# EVB-ANNA-B5_SCHEM_0004_Connectors_Memory.net
KiCad netlist of a schematic drawn in Altium Designer
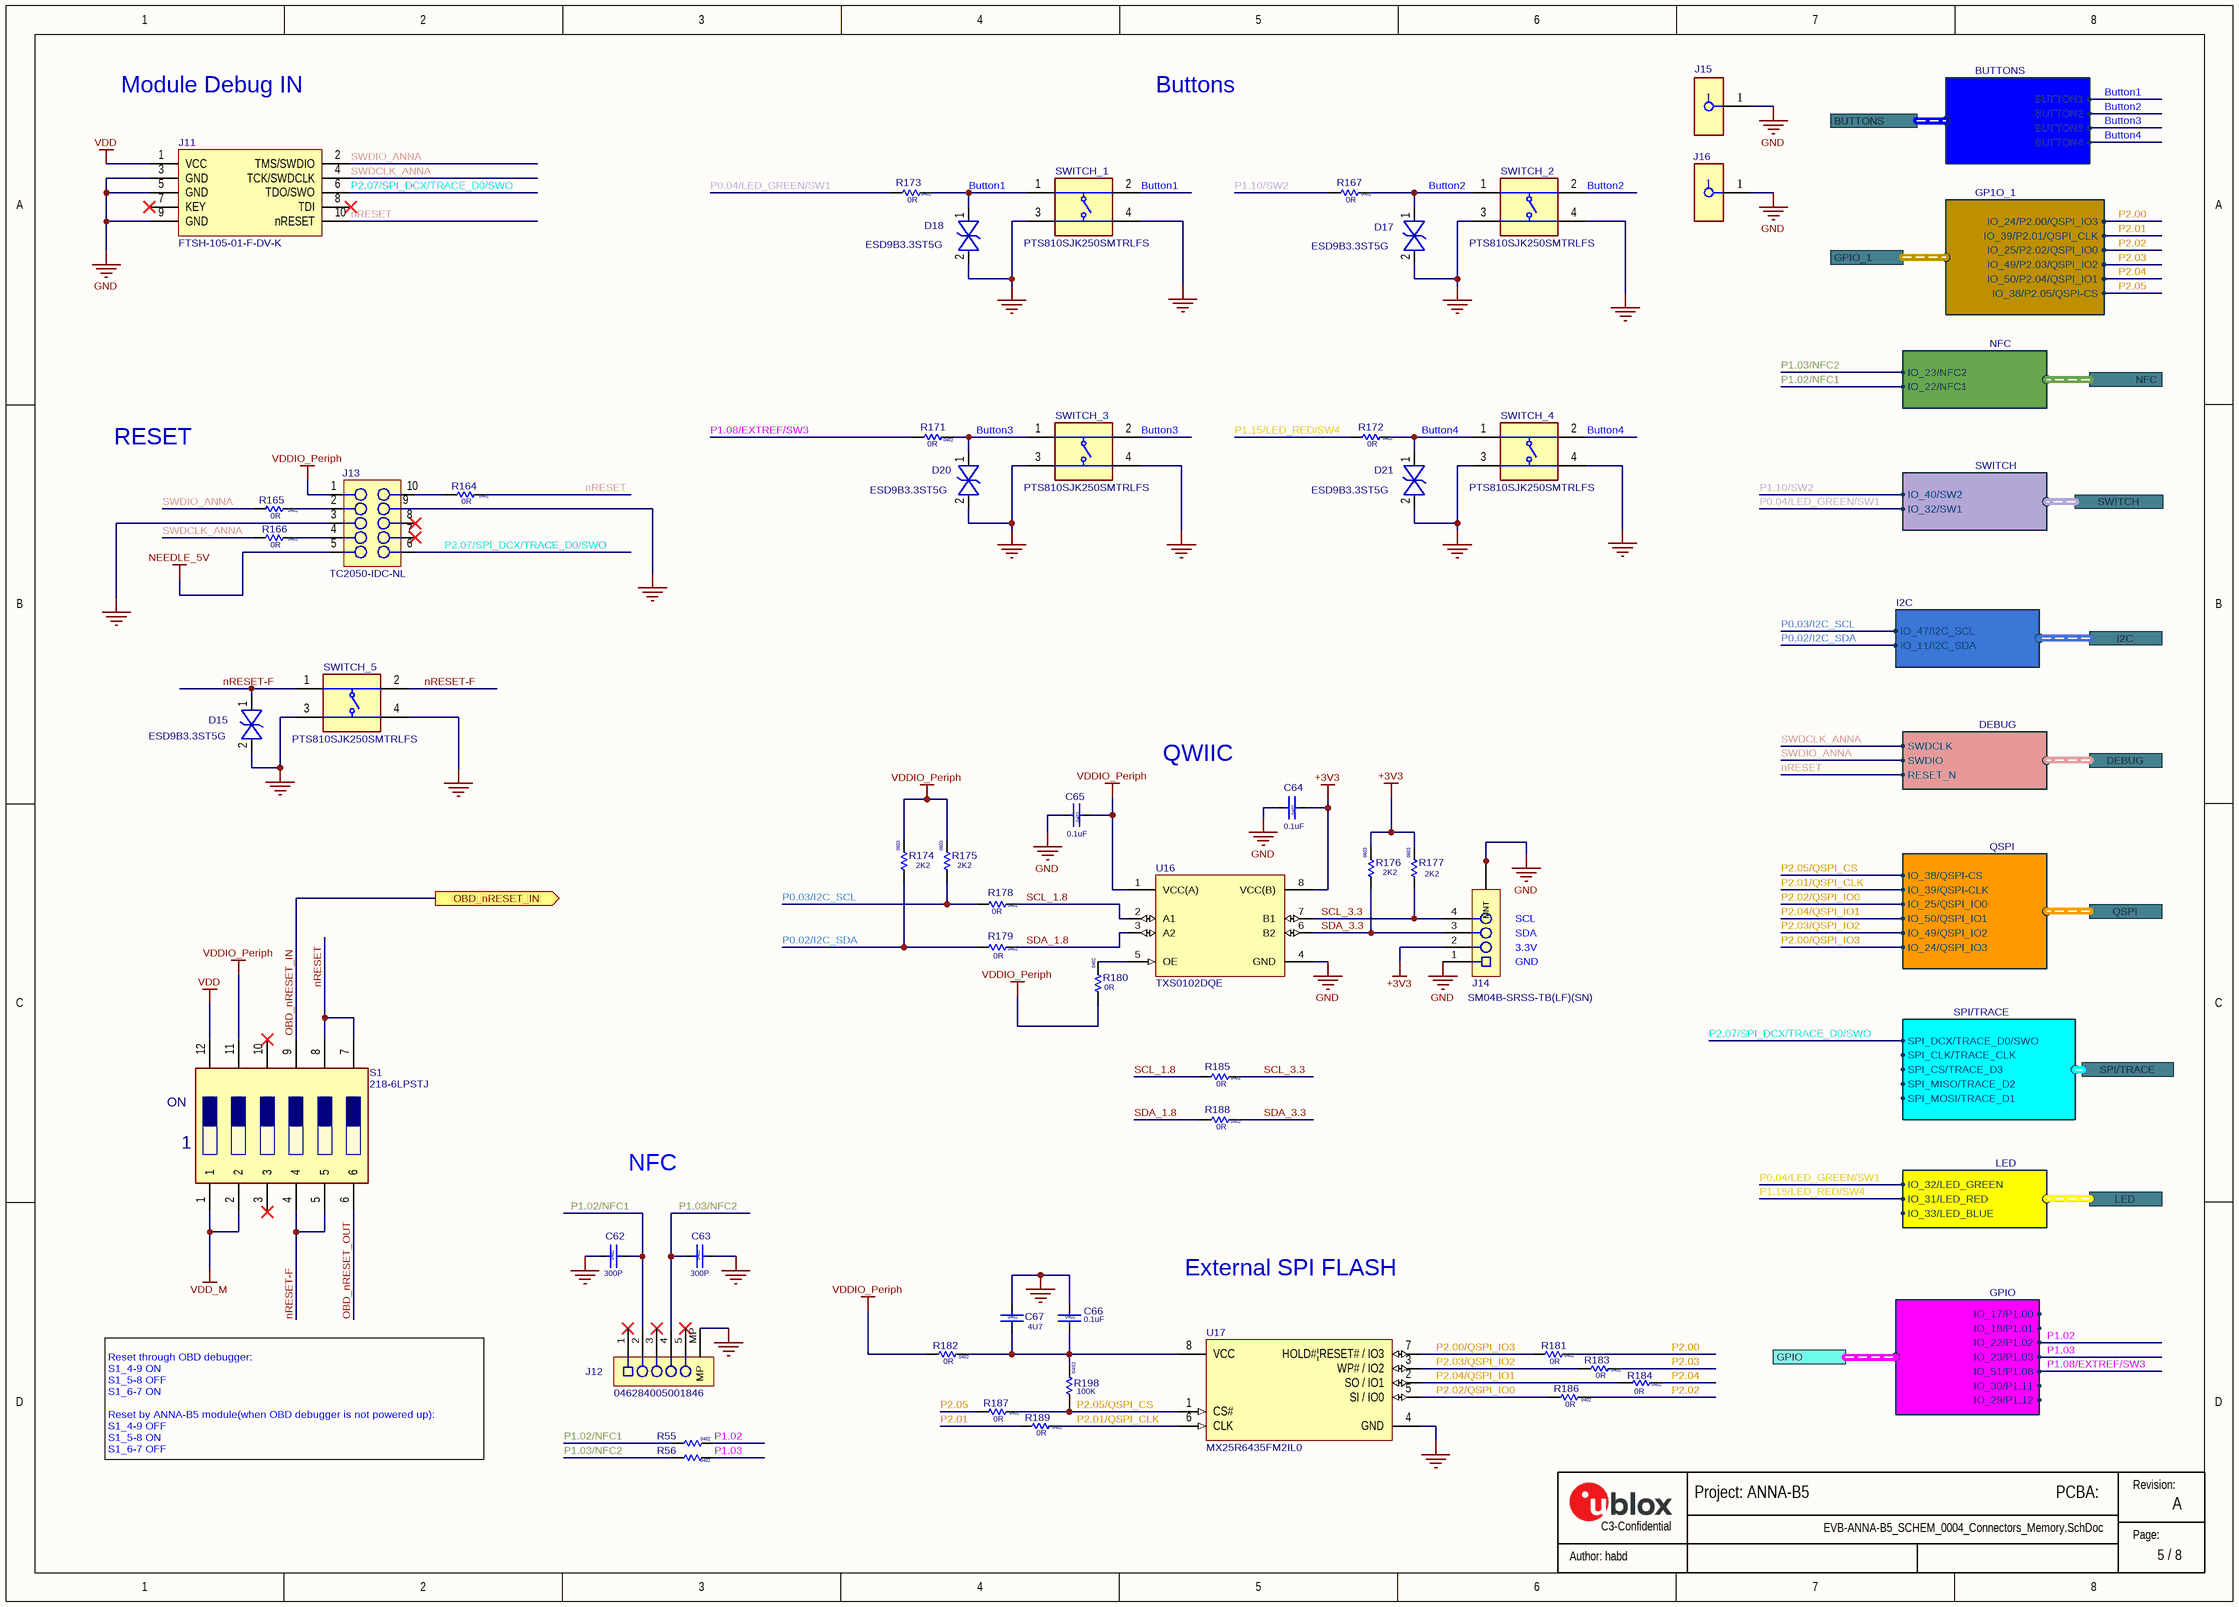
[diagram p0: EVB-ANNA-B5_SCHEM_0004_Connectors_Memory.SchDoc]

(export (version "E")
  (design (tool "Eeschema 10.0.6"))
  (components
    (comp (ref "C62")
      (value "300P")
      (footprint "Cap 0402 HD")
      (description "CAP CER C0G 0402 300P 50V")
      (fields
        (field (name "SIZE") "0402")
        (field (name "PART NUMBER") "UBXH01-0000594")
        (field (name "MANUFACTURER") "Murata Manufacturing Company, Ltd.")
        (field (name "EDITOR") "eric.moog")
      )
      (libsource (lib "UBX_Parts_DB_Lib") (part "Cap Chip"))
    )
    (comp (ref "C63")
      (value "300P")
      (footprint "Cap 0402 HD")
      (description "CAP CER C0G 0402 300P 50V")
      (fields
        (field (name "SIZE") "0402")
        (field (name "PART NUMBER") "UBXH01-0000594")
        (field (name "MANUFACTURER") "Murata Manufacturing Company, Ltd.")
        (field (name "EDITOR") "eric.moog")
      )
      (libsource (lib "UBX_Parts_DB_Lib") (part "Cap Chip"))
    )
    (comp (ref "C64")
      (value "0.1uF")
      (footprint "Cap 0402 HD")
      (description "Cap, Ceramic 0.1uF 10V 10% X5R 0402")
      (fields
        (field (name "SIZE") "0402")
        (field (name "PART NUMBER") "120-00016")
        (field (name "MANUFACTURER") "Murata Electronics North America")
      )
      (libsource (lib "Arena_Parts_DB_Lib") (part "Cap Chip"))
    )
    (comp (ref "C65")
      (value "0.1uF")
      (footprint "Cap 0402 HD")
      (description "Cap, Ceramic 0.1uF 10V 10% X5R 0402")
      (fields
        (field (name "SIZE") "0402")
        (field (name "PART NUMBER") "120-00016")
        (field (name "MANUFACTURER") "Murata Electronics North America")
      )
      (libsource (lib "Arena_Parts_DB_Lib") (part "Cap Chip"))
    )
    (comp (ref "C66")
      (value "0.1uF")
      (footprint "Cap 0402 HD")
      (description "Cap, Ceramic 0.1uF 10V 10% X5R 0402")
      (fields
        (field (name "SIZE") "0402")
        (field (name "PART NUMBER") "120-00016")
        (field (name "MANUFACTURER") "Murata Electronics North America")
      )
      (libsource (lib "Arena_Parts_DB_Lib") (part "Cap Chip"))
    )
    (comp (ref "C67")
      (value "4U7")
      (footprint "Cap 0402 HD")
      (description "CAP CER X5R 0402 4U7 20% 10V")
      (fields
        (field (name "SIZE") "0402")
        (field (name "PART NUMBER") "UBXH01-0000243")
        (field (name "TOLERANCE") "20%")
        (field (name "EDITOR") "martin.pilik")
        (field (name "RELEASED BY") "fabrice.bret-dibat")
      )
      (libsource (lib "UBX_Parts_DB_Lib") (part "Cap Chip"))
    )
    (comp (ref "D15")
      (value "110-00019")
      (footprint "SOD-923")
      (description "ESD9B3.3ST5G")
      (fields
        (field (name "MANUFACTURER") "ON Semiconductor")
        (field (name "MANUFACTURER P/N") "ESD9B3.3ST5G")
        (field (name "VOLTAGE") "3.3V")
      )
      (libsource (lib "Arena_Parts_DB_Lib") (part "Diode_TVS"))
    )
    (comp (ref "D17")
      (value "110-00019")
      (footprint "SOD-923")
      (description "ESD9B3.3ST5G")
      (fields
        (field (name "MANUFACTURER") "ON Semiconductor")
        (field (name "MANUFACTURER P/N") "ESD9B3.3ST5G")
        (field (name "VOLTAGE") "3.3V")
      )
      (libsource (lib "Arena_Parts_DB_Lib") (part "Diode_TVS"))
    )
    (comp (ref "D18")
      (value "110-00019")
      (footprint "SOD-923")
      (description "ESD9B3.3ST5G")
      (fields
        (field (name "MANUFACTURER") "ON Semiconductor")
        (field (name "MANUFACTURER P/N") "ESD9B3.3ST5G")
        (field (name "VOLTAGE") "3.3V")
      )
      (libsource (lib "Arena_Parts_DB_Lib") (part "Diode_TVS"))
    )
    (comp (ref "D20")
      (value "110-00019")
      (footprint "SOD-923")
      (description "ESD9B3.3ST5G")
      (fields
        (field (name "MANUFACTURER") "ON Semiconductor")
        (field (name "MANUFACTURER P/N") "ESD9B3.3ST5G")
        (field (name "VOLTAGE") "3.3V")
      )
      (libsource (lib "Arena_Parts_DB_Lib") (part "Diode_TVS"))
    )
    (comp (ref "D21")
      (value "110-00019")
      (footprint "SOD-923")
      (description "ESD9B3.3ST5G")
      (fields
        (field (name "MANUFACTURER") "ON Semiconductor")
        (field (name "MANUFACTURER P/N") "ESD9B3.3ST5G")
        (field (name "VOLTAGE") "3.3V")
      )
      (libsource (lib "Arena_Parts_DB_Lib") (part "Diode_TVS"))
    )
    (comp (ref "J11")
      (value "130-00099")
      (footprint "HDR.050P-10Pin-2x5-SMT_Key")
      (description "Header 0.05\" 10Pin 2Row SMD Black")
      (fields (field (name "MANUFACTURER") "Samtec") (field (name "MANUFACTURER P/N") "FTSH-105-01-F-DV-K"))
      (libsource (lib "Arena_Parts_DB_Lib") (part "JTAG-10Pin"))
    )
    (comp (ref "J12")
      (value "UBXH04-0000798")
      (footprint "AVX/Kyocera - 046284005001846")
      (description "0.50MM PITCH SMD RA FFC FPC CONN 5 -PIN 50V 400mA")
      (fields
        (field (name "MANUFACTURER P/N") "046284005001846")
        (field (name "VOLTAGE") "50V")
        (field (name "MANUFACTURER") "AVX")
        (field (name "EDITOR") "eric.moog")
      )
      (libsource (lib "UBX_Parts_DB_Lib") (part "CON-5Pin_1Row-046284005001846"))
    )
    (comp (ref "J13")
      (value "TC2050-IDC-NL")
      (footprint "TC2050-IDC-NL")
      (description "CON PADS FOR CBL PLUG-OF-NAILS 10-PIN NO LEGS")
      (fields
        (field (name "MANUFACTURER P/N") "TC2050-IDC-NL")
        (field (name "MANUFACTURER") "TAG Connect")
        (field (name "ADDED BY") "Paul B")
      )
      (libsource (lib "LEGACY_Rigado_AltiumLib") (part "CON-10Pin_2Row_ALT"))
    )
    (comp (ref "J14")
      (value "UBXH04-0000797")
      (footprint "SM04B-SRSS-TB")
      (description "CONN JST SH SERIES SMT 4 POS MALE 1MM RA 50V 1A")
      (fields
        (field (name "MANUFACTURER PART NUMBER 1") "SM04B-SRSS-TB(LF)(SN)")
        (field (name "VOLTAGE") "None")
        (field (name "MANUFACTURER") "JST")
        (field (name "EDITOR") "eric.moog")
      )
      (libsource (lib "UBX_Parts_DB_Lib") (part "SM04B-SRSS-TB"))
    )
    (comp (ref "J15")
      (value "~")
      (footprint "Harwin_0_MFG")
      (libsource (lib "Conn_Harwin_S1751-46R_eec") (part "S1751-46R"))
    )
    (comp (ref "J16")
      (value "~")
      (footprint "Harwin_0_MFG")
      (libsource (lib "Conn_Harwin_S1751-46R_eec") (part "S1751-46R"))
    )
    (comp (ref "R55")
      (value "UBXH18-0003002")
      (footprint "RES 0402 HD")
      (description "RES THICK FILM CHIP 0402 0R 0 100mW")
      (fields
        (field (name "SIZE") "0402")
        (field (name "TOLERANCE") "0")
        (field (name "MANUFACTURER") "KOA")
        (field (name "EDITOR") "charlotte.biber")
        (field (name "RELEASED BY") "peter.mueller")
      )
      (libsource (lib "UBX_Parts_DB_Lib") (part "Res sm"))
    )
    (comp (ref "R56")
      (value "UBXH18-0003002")
      (footprint "RES 0402 HD")
      (description "RES THICK FILM CHIP 0402 0R 0 100mW")
      (fields
        (field (name "SIZE") "0402")
        (field (name "TOLERANCE") "0")
        (field (name "MANUFACTURER") "KOA")
        (field (name "EDITOR") "charlotte.biber")
        (field (name "RELEASED BY") "peter.mueller")
      )
      (libsource (lib "UBX_Parts_DB_Lib") (part "Res sm"))
    )
    (comp (ref "R164")
      (value "0R")
      (footprint "RES 0402 HD")
      (description "RES THICK FILM CHIP 0402 0R 0 100mW")
      (fields
        (field (name "SIZE") "0402")
        (field (name "PART NUMBER") "UBXH18-0003002")
        (field (name "TOLERANCE") "0")
        (field (name "EDITOR") "charlotte.biber")
        (field (name "RELEASED BY") "peter.mueller")
      )
      (libsource (lib "UBX_Parts_DB_Lib") (part "Res sm"))
    )
    (comp (ref "R165")
      (value "0R")
      (footprint "RES 0402 HD")
      (description "RES THICK FILM CHIP 0402 0R 0 100mW")
      (fields
        (field (name "SIZE") "0402")
        (field (name "PART NUMBER") "UBXH18-0003002")
        (field (name "TOLERANCE") "0")
        (field (name "EDITOR") "charlotte.biber")
        (field (name "RELEASED BY") "peter.mueller")
      )
      (libsource (lib "UBX_Parts_DB_Lib") (part "Res sm"))
    )
    (comp (ref "R166")
      (value "0R")
      (footprint "RES 0402 HD")
      (description "RES THICK FILM CHIP 0402 0R 0 100mW")
      (fields
        (field (name "SIZE") "0402")
        (field (name "PART NUMBER") "UBXH18-0003002")
        (field (name "TOLERANCE") "0")
        (field (name "EDITOR") "charlotte.biber")
        (field (name "RELEASED BY") "peter.mueller")
      )
      (libsource (lib "UBX_Parts_DB_Lib") (part "Res sm"))
    )
    (comp (ref "R167")
      (value "0R")
      (footprint "RES 0402 HD")
      (description "RES THICK FILM CHIP 0402 0R 0 100mW")
      (fields
        (field (name "SIZE") "0402")
        (field (name "PART NUMBER") "UBXH18-0003002")
        (field (name "TOLERANCE") "0")
        (field (name "EDITOR") "charlotte.biber")
        (field (name "RELEASED BY") "peter.mueller")
      )
      (libsource (lib "UBX_Parts_DB_Lib") (part "Res sm"))
    )
    (comp (ref "R171")
      (value "0R")
      (footprint "RES 0402 HD")
      (description "RES THICK FILM CHIP 0402 0R 0 100mW")
      (fields
        (field (name "SIZE") "0402")
        (field (name "PART NUMBER") "UBXH18-0003002")
        (field (name "TOLERANCE") "0")
        (field (name "EDITOR") "charlotte.biber")
        (field (name "RELEASED BY") "peter.mueller")
      )
      (libsource (lib "UBX_Parts_DB_Lib") (part "Res sm"))
    )
    (comp (ref "R172")
      (value "0R")
      (footprint "RES 0402 HD")
      (description "RES THICK FILM CHIP 0402 0R 0 100mW")
      (fields
        (field (name "SIZE") "0402")
        (field (name "PART NUMBER") "UBXH18-0003002")
        (field (name "TOLERANCE") "0")
        (field (name "EDITOR") "charlotte.biber")
        (field (name "RELEASED BY") "peter.mueller")
      )
      (libsource (lib "UBX_Parts_DB_Lib") (part "Res sm"))
    )
    (comp (ref "R173")
      (value "0R")
      (footprint "RES 0402 HD")
      (description "RES THICK FILM CHIP 0402 0R 0 100mW")
      (fields
        (field (name "SIZE") "0402")
        (field (name "PART NUMBER") "UBXH18-0003002")
        (field (name "TOLERANCE") "0")
        (field (name "EDITOR") "charlotte.biber")
        (field (name "RELEASED BY") "peter.mueller")
      )
      (libsource (lib "UBX_Parts_DB_Lib") (part "Res sm"))
    )
    (comp (ref "R174")
      (value "2K2")
      (footprint "RES_0603_1700Lx950Wx600H_600x1000Pad_800G_FLX")
      (description "RES THICK FILM CHIP 0603 2K2 5% 100mW")
      (fields
        (field (name "SIZE") "0603")
        (field (name "PART NUMBER") "UBXH18-0007081")
        (field (name "TOLERANCE") "5%")
        (field (name "EDITOR") "roland.rust")
        (field (name "RELEASED BY") "roland.rust")
      )
      (libsource (lib "UBX_Parts_DB_Lib") (part "Res sm"))
    )
    (comp (ref "R175")
      (value "2K2")
      (footprint "RES_0603_1700Lx950Wx600H_600x1000Pad_800G_FLX")
      (description "RES THICK FILM CHIP 0603 2K2 5% 100mW")
      (fields
        (field (name "SIZE") "0603")
        (field (name "PART NUMBER") "UBXH18-0007081")
        (field (name "TOLERANCE") "5%")
        (field (name "EDITOR") "roland.rust")
        (field (name "RELEASED BY") "roland.rust")
      )
      (libsource (lib "UBX_Parts_DB_Lib") (part "Res sm"))
    )
    (comp (ref "R176")
      (value "2K2")
      (footprint "RES_0603_1700Lx950Wx600H_600x1000Pad_800G_FLX")
      (description "RES THICK FILM CHIP 0603 2K2 5% 100mW")
      (fields
        (field (name "SIZE") "0603")
        (field (name "PART NUMBER") "UBXH18-0007081")
        (field (name "TOLERANCE") "5%")
        (field (name "EDITOR") "roland.rust")
        (field (name "RELEASED BY") "roland.rust")
      )
      (libsource (lib "UBX_Parts_DB_Lib") (part "Res sm"))
    )
    (comp (ref "R177")
      (value "2K2")
      (footprint "RES_0603_1700Lx950Wx600H_600x1000Pad_800G_FLX")
      (description "RES THICK FILM CHIP 0603 2K2 5% 100mW")
      (fields
        (field (name "SIZE") "0603")
        (field (name "PART NUMBER") "UBXH18-0007081")
        (field (name "TOLERANCE") "5%")
        (field (name "EDITOR") "roland.rust")
        (field (name "RELEASED BY") "roland.rust")
      )
      (libsource (lib "UBX_Parts_DB_Lib") (part "Res sm"))
    )
    (comp (ref "R178")
      (value "0R")
      (footprint "RES 0402 HD")
      (description "RES THICK FILM CHIP 0402 0R 0 100mW")
      (fields
        (field (name "SIZE") "0402")
        (field (name "PART NUMBER") "UBXH18-0003002")
        (field (name "TOLERANCE") "0")
        (field (name "EDITOR") "charlotte.biber")
        (field (name "RELEASED BY") "peter.mueller")
      )
      (libsource (lib "UBX_Parts_DB_Lib") (part "Res sm"))
    )
    (comp (ref "R179")
      (value "0R")
      (footprint "RES 0402 HD")
      (description "RES THICK FILM CHIP 0402 0R 0 100mW")
      (fields
        (field (name "SIZE") "0402")
        (field (name "PART NUMBER") "UBXH18-0003002")
        (field (name "TOLERANCE") "0")
        (field (name "EDITOR") "charlotte.biber")
        (field (name "RELEASED BY") "peter.mueller")
      )
      (libsource (lib "UBX_Parts_DB_Lib") (part "Res sm"))
    )
    (comp (ref "R180")
      (value "0R")
      (footprint "RES 0402 HD")
      (description "RES THICK FILM CHIP 0402 0R 0 100mW")
      (fields
        (field (name "SIZE") "0402")
        (field (name "PART NUMBER") "UBXH18-0003002")
        (field (name "TOLERANCE") "0")
        (field (name "EDITOR") "charlotte.biber")
        (field (name "RELEASED BY") "peter.mueller")
      )
      (libsource (lib "UBX_Parts_DB_Lib") (part "Res sm"))
    )
    (comp (ref "R181")
      (value "0R")
      (footprint "RES 0402 HD")
      (description "RES THICK FILM CHIP 0402 0R 0 100mW")
      (fields
        (field (name "SIZE") "0402")
        (field (name "PART NUMBER") "UBXH18-0003002")
        (field (name "TOLERANCE") "0")
        (field (name "EDITOR") "charlotte.biber")
        (field (name "RELEASED BY") "peter.mueller")
      )
      (libsource (lib "UBX_Parts_DB_Lib") (part "Res sm"))
    )
    (comp (ref "R182")
      (value "0R")
      (footprint "RES 0402 HD")
      (description "RES THICK FILM CHIP 0402 0R 0 100mW")
      (fields
        (field (name "SIZE") "0402")
        (field (name "PART NUMBER") "UBXH18-0003002")
        (field (name "TOLERANCE") "0")
        (field (name "EDITOR") "charlotte.biber")
        (field (name "RELEASED BY") "peter.mueller")
      )
      (libsource (lib "UBX_Parts_DB_Lib") (part "Res sm"))
    )
    (comp (ref "R183")
      (value "0R")
      (footprint "RES 0402 HD")
      (description "RES THICK FILM CHIP 0402 0R 0 100mW")
      (fields
        (field (name "SIZE") "0402")
        (field (name "PART NUMBER") "UBXH18-0003002")
        (field (name "TOLERANCE") "0")
        (field (name "EDITOR") "charlotte.biber")
        (field (name "RELEASED BY") "peter.mueller")
      )
      (libsource (lib "UBX_Parts_DB_Lib") (part "Res sm"))
    )
    (comp (ref "R184")
      (value "0R")
      (footprint "RES 0402 HD")
      (description "RES THICK FILM CHIP 0402 0R 0 100mW")
      (fields
        (field (name "SIZE") "0402")
        (field (name "PART NUMBER") "UBXH18-0003002")
        (field (name "TOLERANCE") "0")
        (field (name "EDITOR") "charlotte.biber")
        (field (name "RELEASED BY") "peter.mueller")
      )
      (libsource (lib "UBX_Parts_DB_Lib") (part "Res sm"))
    )
    (comp (ref "R185")
      (value "0R")
      (footprint "RES 0402 HD")
      (description "RES THICK FILM CHIP 0402 0R 0 100mW")
      (fields
        (field (name "SIZE") "0402")
        (field (name "PART NUMBER") "UBXH18-0003002")
        (field (name "TOLERANCE") "0")
        (field (name "EDITOR") "charlotte.biber")
        (field (name "RELEASED BY") "peter.mueller")
      )
      (libsource (lib "UBX_Parts_DB_Lib") (part "Res sm"))
    )
    (comp (ref "R186")
      (value "0R")
      (footprint "RES 0402 HD")
      (description "RES THICK FILM CHIP 0402 0R 0 100mW")
      (fields
        (field (name "SIZE") "0402")
        (field (name "PART NUMBER") "UBXH18-0003002")
        (field (name "TOLERANCE") "0")
        (field (name "EDITOR") "charlotte.biber")
        (field (name "RELEASED BY") "peter.mueller")
      )
      (libsource (lib "UBX_Parts_DB_Lib") (part "Res sm"))
    )
    (comp (ref "R187")
      (value "0R")
      (footprint "RES 0402 HD")
      (description "RES THICK FILM CHIP 0402 0R 0 100mW")
      (fields
        (field (name "SIZE") "0402")
        (field (name "PART NUMBER") "UBXH18-0003002")
        (field (name "TOLERANCE") "0")
        (field (name "EDITOR") "charlotte.biber")
        (field (name "RELEASED BY") "peter.mueller")
      )
      (libsource (lib "UBX_Parts_DB_Lib") (part "Res sm"))
    )
    (comp (ref "R188")
      (value "0R")
      (footprint "RES 0402 HD")
      (description "RES THICK FILM CHIP 0402 0R 0 100mW")
      (fields
        (field (name "SIZE") "0402")
        (field (name "PART NUMBER") "UBXH18-0003002")
        (field (name "TOLERANCE") "0")
        (field (name "EDITOR") "charlotte.biber")
        (field (name "RELEASED BY") "peter.mueller")
      )
      (libsource (lib "UBX_Parts_DB_Lib") (part "Res sm"))
    )
    (comp (ref "R189")
      (value "0R")
      (footprint "RES 0402 HD")
      (description "RES THICK FILM CHIP 0402 0R 0 100mW")
      (fields
        (field (name "SIZE") "0402")
        (field (name "PART NUMBER") "UBXH18-0003002")
        (field (name "TOLERANCE") "0")
        (field (name "EDITOR") "charlotte.biber")
        (field (name "RELEASED BY") "peter.mueller")
      )
      (libsource (lib "UBX_Parts_DB_Lib") (part "Res sm"))
    )
    (comp (ref "R198")
      (value "100K")
      (footprint "RES 0402 HD")
      (description "RES THICK FILM CHIP 0402 100K 1% 63mW")
      (fields
        (field (name "SIZE") "0402")
        (field (name "PART NUMBER") "UBXH18-0000005")
        (field (name "TOLERANCE") "1%")
        (field (name "EDITOR") "dario.antonaz")
        (field (name "RELEASED BY") "sandro.sestan")
      )
      (libsource (lib "UBX_Parts_DB_Lib") (part "Res sm"))
    )
    (comp (ref "S1")
      (value "218-6LPSTJ")
      (footprint "2186LPSTJ")
      (description "Switch")
      (fields (field (name "MOUSER PART NUMBER") "774-2186LPSTJ"))
      (libsource (lib "SamacSys") (part "218-6LPSTJ"))
    )
    (comp (ref "SWITCH_1")
      (value "~")
      (footprint "PTS810SJG250SMTRLFS")
      (description "Switch")
      (fields
        (field (name "MANUFACTURER_PART_NUMBER") "PTS810SJK250SMTRLFS")
        (field (name "MOUSER PART NUMBER") "611-PTS810SJK250SMTR")
      )
      (libsource (lib "SamacSys") (part "PTS810SJK250SMTRLFS"))
    )
    (comp (ref "SWITCH_2")
      (value "~")
      (footprint "PTS810SJG250SMTRLFS")
      (description "Switch")
      (fields
        (field (name "MANUFACTURER_PART_NUMBER") "PTS810SJK250SMTRLFS")
        (field (name "MOUSER PART NUMBER") "611-PTS810SJK250SMTR")
      )
      (libsource (lib "SamacSys") (part "PTS810SJK250SMTRLFS"))
    )
    (comp (ref "SWITCH_3")
      (value "~")
      (footprint "PTS810SJG250SMTRLFS")
      (description "Switch")
      (fields
        (field (name "MANUFACTURER_PART_NUMBER") "PTS810SJK250SMTRLFS")
        (field (name "MOUSER PART NUMBER") "611-PTS810SJK250SMTR")
      )
      (libsource (lib "SamacSys") (part "PTS810SJK250SMTRLFS"))
    )
    (comp (ref "SWITCH_4")
      (value "~")
      (footprint "PTS810SJG250SMTRLFS")
      (description "Switch")
      (fields
        (field (name "MANUFACTURER_PART_NUMBER") "PTS810SJK250SMTRLFS")
        (field (name "MOUSER PART NUMBER") "611-PTS810SJK250SMTR")
      )
      (libsource (lib "SamacSys") (part "PTS810SJK250SMTRLFS"))
    )
    (comp (ref "SWITCH_5")
      (value "~")
      (footprint "PTS810SJG250SMTRLFS")
      (description "Switch")
      (fields
        (field (name "MANUFACTURER_PART_NUMBER") "PTS810SJK250SMTRLFS")
        (field (name "MOUSER PART NUMBER") "611-PTS810SJK250SMTR")
      )
      (libsource (lib "SamacSys") (part "PTS810SJK250SMTRLFS"))
    )
    (comp (ref "U16")
      (value "TXS0102DQE")
      (footprint "DQE0008A")
      (description "TXS0102 2-BIT BIDIRECTIONAL VOLTAGE-LEVEL TRANSLATOR X2SON-8 TXS0102DQE 5.5V")
      (fields
        (field (name "PART NUMBER") "UBXH10-0000108")
        (field (name "MANUFACTURER") "Texas Instruments")
        (field (name "EDITOR") "eric.moog")
      )
      (libsource (lib "UBX_Parts_DB_Lib") (part "TXS0102DQE"))
    )
    (comp (ref "U17")
      (value "UBXH13-0000149")
      (footprint "SOIC-8")
      (description "MACRONIX MX25R6435FM2IL0 64MBIT SERIAL QUAD I/O SPI FLASH MEMORY 1.65 - 3.6V 8-SOP (200mil)")
      (fields (field (name "MANUFACTURER P/N") "MX25R6435FM2IL0") (field (name "OWNER") "Hozaifa Abdelgadir"))
      (libsource (lib "UBX_Arena") (part "SPI_Flash_Memory_8Pin"))
    )
  )
  (nets
    (net (code "11") (name "+3V3") (class "Default")
      (node (ref "C64") (pin "1") (pinfunction "1_1") (pintype "passive"))
      (node (ref "J14") (pin "2") (pinfunction "2_2") (pintype "passive"))
      (node (ref "R176") (pin "2") (pinfunction "2_2") (pintype "passive"))
      (node (ref "R177") (pin "2") (pinfunction "2_2") (pintype "passive"))
      (node (ref "U16") (pin "8") (pinfunction "VCC(B)_8") (pintype "power_in"))
    )
    (net (code "12") (name "/Button1") (class "Default")
      (node (ref "D18") (pin "1") (pintype "passive"))
      (node (ref "R173") (pin "1") (pinfunction "1_1") (pintype "passive"))
      (node (ref "SWITCH_1") (pin "1") (pinfunction "1_1") (pintype "passive"))
      (node (ref "SWITCH_1") (pin "2") (pinfunction "2_2") (pintype "passive"))
    )
    (net (code "13") (name "/Button2") (class "Default")
      (node (ref "D17") (pin "1") (pintype "passive"))
      (node (ref "R167") (pin "1") (pinfunction "1_1") (pintype "passive"))
      (node (ref "SWITCH_2") (pin "1") (pinfunction "1_1") (pintype "passive"))
      (node (ref "SWITCH_2") (pin "2") (pinfunction "2_2") (pintype "passive"))
    )
    (net (code "14") (name "/Button3") (class "Default")
      (node (ref "D20") (pin "1") (pintype "passive"))
      (node (ref "R171") (pin "1") (pinfunction "1_1") (pintype "passive"))
      (node (ref "SWITCH_3") (pin "1") (pinfunction "1_1") (pintype "passive"))
      (node (ref "SWITCH_3") (pin "2") (pinfunction "2_2") (pintype "passive"))
    )
    (net (code "15") (name "/Button4") (class "Default")
      (node (ref "D21") (pin "1") (pintype "passive"))
      (node (ref "R172") (pin "1") (pinfunction "1_1") (pintype "passive"))
      (node (ref "SWITCH_4") (pin "1") (pinfunction "1_1") (pintype "passive"))
      (node (ref "SWITCH_4") (pin "2") (pinfunction "2_2") (pintype "passive"))
    )
    (net (code "16") (name "/OBD_nRESET_IN") (class "Default")
      (node (ref "S1") (pin "9") (pintype "passive"))
    )
    (net (code "17") (name "/OBD_nRESET_OUT") (class "Default")
      (node (ref "S1") (pin "6") (pinfunction "6_6") (pintype "passive"))
    )
    (net (code "18") (name "/P0.02{slash}I2C_SDA") (class "Default")
      (node (ref "R174") (pin "1") (pinfunction "1_1") (pintype "passive"))
      (node (ref "R179") (pin "2") (pinfunction "2_2") (pintype "passive"))
    )
    (net (code "19") (name "/P0.03{slash}I2C_SCL") (class "Default")
      (node (ref "R175") (pin "1") (pinfunction "1_1") (pintype "passive"))
      (node (ref "R178") (pin "2") (pinfunction "2_2") (pintype "passive"))
    )
    (net (code "20") (name "/P0.04{slash}LED_GREEN{slash}SW1") (class "Default")
      (node (ref "R173") (pin "2") (pinfunction "2_2") (pintype "passive"))
    )
    (net (code "21") (name "/P1.02") (class "Default")
      (node (ref "R55") (pin "1") (pinfunction "1_1") (pintype "passive"))
    )
    (net (code "22") (name "/P1.02{slash}NFC1") (class "Default")
      (node (ref "C62") (pin "2") (pinfunction "2_2") (pintype "passive"))
      (node (ref "J12") (pin "2") (pinfunction "2_2") (pintype "passive"))
      (node (ref "R55") (pin "2") (pinfunction "2_2") (pintype "passive"))
    )
    (net (code "23") (name "/P1.03") (class "Default")
      (node (ref "R56") (pin "1") (pinfunction "1_1") (pintype "passive"))
    )
    (net (code "24") (name "/P1.03{slash}NFC2") (class "Default")
      (node (ref "C63") (pin "1") (pinfunction "1_1") (pintype "passive"))
      (node (ref "J12") (pin "4") (pinfunction "4_4") (pintype "passive"))
      (node (ref "R56") (pin "2") (pinfunction "2_2") (pintype "passive"))
    )
    (net (code "25") (name "/P1.08{slash}EXTREF{slash}SW3") (class "Default")
      (node (ref "R171") (pin "2") (pinfunction "2_2") (pintype "passive"))
    )
    (net (code "26") (name "/P1.10{slash}SW2") (class "Default")
      (node (ref "R167") (pin "2") (pinfunction "2_2") (pintype "passive"))
    )
    (net (code "27") (name "/P1.15{slash}LED_RED{slash}SW4") (class "Default")
      (node (ref "R172") (pin "2") (pinfunction "2_2") (pintype "passive"))
    )
    (net (code "28") (name "/P2.00") (class "Default")
      (node (ref "R181") (pin "1") (pinfunction "1_1") (pintype "passive"))
    )
    (net (code "29") (name "/P2.00{slash}QSPI_IO3") (class "Default")
      (node (ref "R181") (pin "2") (pinfunction "2_2") (pintype "passive"))
      (node (ref "U17") (pin "7") (pinfunction "HOLD#¦RESET#_/_IO3_7") (pintype "bidirectional"))
    )
    (net (code "30") (name "/P2.01") (class "Default")
      (node (ref "R189") (pin "2") (pinfunction "2_2") (pintype "passive"))
    )
    (net (code "31") (name "/P2.01{slash}QSPI_CLK") (class "Default")
      (node (ref "R189") (pin "1") (pinfunction "1_1") (pintype "passive"))
      (node (ref "U17") (pin "6") (pinfunction "CLK_6") (pintype "input"))
    )
    (net (code "32") (name "/P2.02") (class "Default")
      (node (ref "R186") (pin "1") (pinfunction "1_1") (pintype "passive"))
    )
    (net (code "33") (name "/P2.02{slash}QSPI_IO0") (class "Default")
      (node (ref "R186") (pin "2") (pinfunction "2_2") (pintype "passive"))
      (node (ref "U17") (pin "5") (pinfunction "SI_/_IO0_5") (pintype "bidirectional"))
    )
    (net (code "34") (name "/P2.03") (class "Default")
      (node (ref "R183") (pin "1") (pinfunction "1_1") (pintype "passive"))
    )
    (net (code "35") (name "/P2.03{slash}QSPI_IO2") (class "Default")
      (node (ref "R183") (pin "2") (pinfunction "2_2") (pintype "passive"))
      (node (ref "U17") (pin "3") (pinfunction "WP#_/_IO2_3") (pintype "bidirectional"))
    )
    (net (code "36") (name "/P2.04") (class "Default")
      (node (ref "R184") (pin "1") (pinfunction "1_1") (pintype "passive"))
    )
    (net (code "37") (name "/P2.04{slash}QSPI_IO1") (class "Default")
      (node (ref "R184") (pin "2") (pinfunction "2_2") (pintype "passive"))
      (node (ref "U17") (pin "2") (pinfunction "SO_/_IO1_2") (pintype "bidirectional"))
    )
    (net (code "38") (name "/P2.05") (class "Default")
      (node (ref "R187") (pin "2") (pinfunction "2_2") (pintype "passive"))
    )
    (net (code "39") (name "/P2.05{slash}QSPI_CS") (class "Default")
      (node (ref "R187") (pin "1") (pinfunction "1_1") (pintype "passive"))
      (node (ref "R198") (pin "2") (pinfunction "2_2") (pintype "passive"))
      (node (ref "U17") (pin "1") (pinfunction "CS#_1") (pintype "input"))
    )
    (net (code "40") (name "/P2.07{slash}SPI_DCX{slash}TRACE_D0{slash}SWO") (class "Default")
      (node (ref "J11") (pin "6") (pinfunction "TDO/SWO_6") (pintype "passive"))
      (node (ref "J13") (pin "6") (pintype "passive"))
    )
    (net (code "41") (name "/SCL_1.8") (class "Default")
      (node (ref "R178") (pin "1") (pinfunction "1_1") (pintype "passive"))
      (node (ref "R185") (pin "2") (pinfunction "2_2") (pintype "passive"))
      (node (ref "U16") (pin "2") (pinfunction "A1_2") (pintype "bidirectional"))
    )
    (net (code "42") (name "/SCL_3.3") (class "Default")
      (node (ref "J14") (pin "4") (pinfunction "4_4") (pintype "passive"))
      (node (ref "R177") (pin "1") (pinfunction "1_1") (pintype "passive"))
      (node (ref "R185") (pin "1") (pinfunction "1_1") (pintype "passive"))
      (node (ref "U16") (pin "7") (pinfunction "B1_7") (pintype "bidirectional"))
    )
    (net (code "43") (name "/SDA_1.8") (class "Default")
      (node (ref "R179") (pin "1") (pinfunction "1_1") (pintype "passive"))
      (node (ref "R188") (pin "2") (pinfunction "2_2") (pintype "passive"))
      (node (ref "U16") (pin "3") (pinfunction "A2_3") (pintype "bidirectional"))
    )
    (net (code "44") (name "/SDA_3.3") (class "Default")
      (node (ref "J14") (pin "3") (pinfunction "3_3") (pintype "passive"))
      (node (ref "R176") (pin "1") (pinfunction "1_1") (pintype "passive"))
      (node (ref "R188") (pin "1") (pinfunction "1_1") (pintype "passive"))
      (node (ref "U16") (pin "6") (pinfunction "B2_6") (pintype "bidirectional"))
    )
    (net (code "45") (name "/SWDCLK_ANNA") (class "Default")
      (node (ref "J11") (pin "4") (pinfunction "TCK/SWDCLK_4") (pintype "passive"))
      (node (ref "R166") (pin "2") (pinfunction "2_2") (pintype "passive"))
    )
    (net (code "46") (name "/SWDIO_ANNA") (class "Default")
      (node (ref "J11") (pin "2") (pinfunction "TMS/SWDIO_2") (pintype "passive"))
      (node (ref "R165") (pin "2") (pinfunction "2_2") (pintype "passive"))
    )
    (net (code "47") (name "/nRESET") (class "Default")
      (node (ref "J11") (pin "10") (pinfunction "nRESET_10") (pintype "passive"))
      (node (ref "R164") (pin "1") (pinfunction "1_1") (pintype "passive"))
      (node (ref "S1") (pin "7") (pintype "passive"))
      (node (ref "S1") (pin "8") (pintype "passive"))
    )
    (net (code "48") (name "/nRESET-F") (class "Default")
      (node (ref "D15") (pin "1") (pintype "passive"))
      (node (ref "S1") (pin "4") (pinfunction "4_4") (pintype "passive"))
      (node (ref "S1") (pin "5") (pinfunction "5_5") (pintype "passive"))
      (node (ref "SWITCH_5") (pin "1") (pinfunction "1_1") (pintype "passive"))
      (node (ref "SWITCH_5") (pin "2") (pinfunction "2_2") (pintype "passive"))
    )
    (net (code "59") (name "GND") (class "Default")
      (node (ref "C62") (pin "1") (pinfunction "1_1") (pintype "passive"))
      (node (ref "C63") (pin "2") (pinfunction "2_2") (pintype "passive"))
      (node (ref "C64") (pin "2") (pinfunction "2_2") (pintype "passive"))
      (node (ref "C65") (pin "2") (pinfunction "2_2") (pintype "passive"))
      (node (ref "C66") (pin "1") (pinfunction "1_1") (pintype "passive"))
      (node (ref "C67") (pin "1") (pinfunction "1_1") (pintype "passive"))
      (node (ref "D15") (pin "2") (pintype "passive"))
      (node (ref "D17") (pin "2") (pintype "passive"))
      (node (ref "D18") (pin "2") (pintype "passive"))
      (node (ref "D20") (pin "2") (pintype "passive"))
      (node (ref "D21") (pin "2") (pintype "passive"))
      (node (ref "J11") (pin "3") (pinfunction "GND_3") (pintype "passive"))
      (node (ref "J11") (pin "5") (pinfunction "GND_5") (pintype "passive"))
      (node (ref "J11") (pin "9") (pinfunction "GND_9") (pintype "passive"))
      (node (ref "J12") (pin "MP") (pinfunction "MP_MP") (pintype "passive"))
      (node (ref "J13") (pin "3") (pintype "passive"))
      (node (ref "J13") (pin "9") (pintype "passive"))
      (node (ref "J14") (pin "1") (pinfunction "1_1") (pintype "passive"))
      (node (ref "J14") (pin "M1") (pinfunction "MNT_M1") (pintype "passive"))
      (node (ref "J14") (pin "M2") (pinfunction "MNT_M2") (pintype "passive"))
      (node (ref "J15") (pin "1") (pinfunction "1_1") (pintype "passive"))
      (node (ref "J16") (pin "1") (pinfunction "1_1") (pintype "passive"))
      (node (ref "SWITCH_1") (pin "3") (pinfunction "3_3") (pintype "passive"))
      (node (ref "SWITCH_1") (pin "4") (pinfunction "4_4") (pintype "passive"))
      (node (ref "SWITCH_2") (pin "3") (pinfunction "3_3") (pintype "passive"))
      (node (ref "SWITCH_2") (pin "4") (pinfunction "4_4") (pintype "passive"))
      (node (ref "SWITCH_3") (pin "3") (pinfunction "3_3") (pintype "passive"))
      (node (ref "SWITCH_3") (pin "4") (pinfunction "4_4") (pintype "passive"))
      (node (ref "SWITCH_4") (pin "3") (pinfunction "3_3") (pintype "passive"))
      (node (ref "SWITCH_4") (pin "4") (pinfunction "4_4") (pintype "passive"))
      (node (ref "SWITCH_5") (pin "3") (pinfunction "3_3") (pintype "passive"))
      (node (ref "SWITCH_5") (pin "4") (pinfunction "4_4") (pintype "passive"))
      (node (ref "U16") (pin "4") (pinfunction "GND_4") (pintype "power_in"))
      (node (ref "U17") (pin "4") (pinfunction "GND_4") (pintype "power_in"))
    )
    (net (code "60") (name "NEEDLE_5V") (class "Default") (node (ref "J13") (pin "5") (pintype "passive")))
    (net (code "61") (name "Net-(J13-Pad2)") (class "Default")
      (node (ref "J13") (pin "2") (pintype "passive"))
      (node (ref "R165") (pin "1") (pinfunction "1_1") (pintype "passive"))
    )
    (net (code "62") (name "Net-(J13-Pad4)") (class "Default")
      (node (ref "J13") (pin "4") (pintype "passive"))
      (node (ref "R166") (pin "1") (pinfunction "1_1") (pintype "passive"))
    )
    (net (code "63") (name "Net-(J13-Pad10)") (class "Default")
      (node (ref "J13") (pin "10") (pintype "passive"))
      (node (ref "R164") (pin "2") (pinfunction "2_2") (pintype "passive"))
    )
    (net (code "64") (name "Net-(U16-OE)") (class "Default")
      (node (ref "R180") (pin "1") (pinfunction "1_1") (pintype "passive"))
      (node (ref "U16") (pin "5") (pinfunction "OE_5") (pintype "input"))
    )
    (net (code "65") (name "Net-(U17-VCC)") (class "Default")
      (node (ref "C66") (pin "2") (pinfunction "2_2") (pintype "passive"))
      (node (ref "C67") (pin "2") (pinfunction "2_2") (pintype "passive"))
      (node (ref "R182") (pin "2") (pinfunction "2_2") (pintype "passive"))
      (node (ref "R198") (pin "1") (pinfunction "1_1") (pintype "passive"))
      (node (ref "U17") (pin "8") (pinfunction "VCC_8") (pintype "power_in"))
    )
    (net (code "66") (name "VDD") (class "Default")
      (node (ref "J11") (pin "1") (pinfunction "VCC_1") (pintype "passive"))
      (node (ref "S1") (pin "12") (pintype "passive"))
    )
    (net (code "67") (name "VDDIO_Periph") (class "Default")
      (node (ref "C65") (pin "1") (pinfunction "1_1") (pintype "passive"))
      (node (ref "J13") (pin "1") (pintype "passive"))
      (node (ref "R174") (pin "2") (pinfunction "2_2") (pintype "passive"))
      (node (ref "R175") (pin "2") (pinfunction "2_2") (pintype "passive"))
      (node (ref "R180") (pin "2") (pinfunction "2_2") (pintype "passive"))
      (node (ref "R182") (pin "1") (pinfunction "1_1") (pintype "passive"))
      (node (ref "S1") (pin "11") (pintype "passive"))
      (node (ref "U16") (pin "1") (pinfunction "VCC(A)_1") (pintype "power_in"))
    )
    (net (code "68") (name "VDD_M") (class "Default")
      (node (ref "S1") (pin "1") (pinfunction "1_1") (pintype "passive"))
      (node (ref "S1") (pin "2") (pinfunction "2_2") (pintype "passive"))
    )
    (net (code "69") (name "unconnected-(J11-KEY-Pad7)") (class "Default")
      (node (ref "J11") (pin "7") (pinfunction "KEY_7") (pintype "passive+no_connect"))
    )
    (net (code "70") (name "unconnected-(J11-TDI-Pad8)") (class "Default")
      (node (ref "J11") (pin "8") (pinfunction "TDI_8") (pintype "passive+no_connect"))
    )
    (net (code "71") (name "unconnected-(J12-Pad1)") (class "Default")
      (node (ref "J12") (pin "1") (pinfunction "1_1") (pintype "passive+no_connect"))
    )
    (net (code "72") (name "unconnected-(J12-Pad3)") (class "Default")
      (node (ref "J12") (pin "3") (pinfunction "3_3") (pintype "passive+no_connect"))
    )
    (net (code "73") (name "unconnected-(J12-Pad5)") (class "Default")
      (node (ref "J12") (pin "5") (pinfunction "5_5") (pintype "passive+no_connect"))
    )
    (net (code "74") (name "unconnected-(J13-Pad7)") (class "Default")
      (node (ref "J13") (pin "7") (pintype "passive+no_connect"))
    )
    (net (code "75") (name "unconnected-(J13-Pad8)") (class "Default")
      (node (ref "J13") (pin "8") (pintype "passive+no_connect"))
    )
    (net (code "76") (name "unconnected-(S1-Pad3)") (class "Default")
      (node (ref "S1") (pin "3") (pinfunction "3_3") (pintype "passive+no_connect"))
    )
    (net (code "77") (name "unconnected-(S1-Pad10)") (class "Default")
      (node (ref "S1") (pin "10") (pintype "passive+no_connect"))
    )
  )
)
